# KHOI_NGUON.net
KiCad netlist of a schematic drawn in Altium Designer
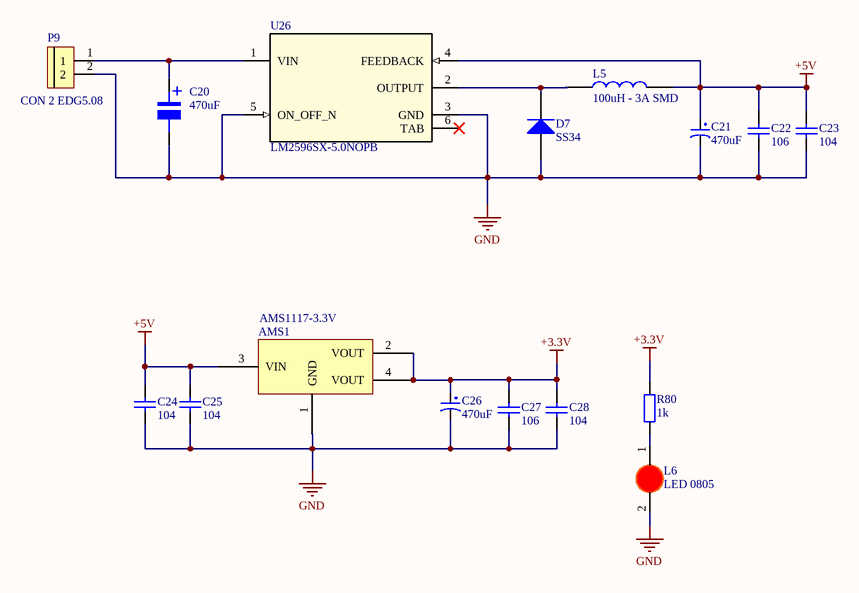
[diagram p0: KHOI_NGUON.SchDoc]

(export (version "E")
  (design (tool "Eeschema 10.0.6"))
  (components
    (comp (ref "AMS1")
      (value "AMS1117-3.3V")
      (footprint "SOT223")
      (description "Dán")
      (libsource (lib "Altium_Lib_by_KhueNguyenCreator") (part "AMS1117 SMD"))
    )
    (comp (ref "C20")
      (value "470uF")
      (footprint "tu nhom 8 (f)")
      (description "Dán")
      (libsource (lib "Altium_Lib_by_KhueNguyenCreator") (part "Tu Nhom 470uF 16V"))
    )
    (comp (ref "C21")
      (value "470uF")
      (footprint "tu hoa 8mm")
      (description "Cắm")
      (libsource (lib "Altium_Lib_by_KhueNguyenCreator") (part "Tu Hoa 470uF 16V 8x11"))
    )
    (comp (ref "C22")
      (value "106")
      (footprint "tu 0805")
      (description "Dán")
      (libsource (lib "Altium_Lib_by_KhueNguyenCreator") (part "Tu 0805 106 16V 10%"))
    )
    (comp (ref "C23")
      (value "104")
      (footprint "tu 0805")
      (description "Dán")
      (libsource (lib "Altium_Lib_by_KhueNguyenCreator") (part "Tu 0805 104 50V 10%"))
    )
    (comp (ref "C24")
      (value "104")
      (footprint "tu 0805")
      (description "Dán")
      (libsource (lib "Altium_Lib_by_KhueNguyenCreator") (part "Tu 0805 104 50V 10%"))
    )
    (comp (ref "C25")
      (value "104")
      (footprint "tu 0805")
      (description "Dán")
      (libsource (lib "Altium_Lib_by_KhueNguyenCreator") (part "Tu 0805 104 50V 10%"))
    )
    (comp (ref "C26")
      (value "470uF")
      (footprint "tu hoa 8mm")
      (description "Cắm")
      (libsource (lib "Altium_Lib_by_KhueNguyenCreator") (part "Tu Hoa 470uF 16V 8x11"))
    )
    (comp (ref "C27")
      (value "106")
      (footprint "tu 0805")
      (description "Dán")
      (libsource (lib "Altium_Lib_by_KhueNguyenCreator") (part "Tu 0805 106 16V 10%"))
    )
    (comp (ref "C28")
      (value "104")
      (footprint "tu 0805")
      (description "Dán")
      (libsource (lib "Altium_Lib_by_KhueNguyenCreator") (part "Tu 0805 104 50V 10%"))
    )
    (comp (ref "D7")
      (value "SS34")
      (footprint "DIODE SMA")
      (description "Dán")
      (libsource (lib "Altium_Lib_by_KhueNguyenCreator") (part "Diode SS34 ( 1N5822 )"))
    )
    (comp (ref "L5")
      (value "100uH - 3A SMD")
      (footprint "Cuon Cam 12x12x10")
      (description "Dán")
      (libsource (lib "Altium_Lib_by_KhueNguyenCreator") (part "CUON CAM 100uH SMD"))
    )
    (comp (ref "L6")
      (value "LED 0805")
      (footprint "LED-0805-Red")
      (description "Dán")
      (libsource (lib "Altium_Lib_by_KhueNguyenCreator") (part "LED 0805 Do"))
    )
    (comp (ref "P9")
      (value "CON 2 EDG5.08")
      (footprint "CON 2 2EDG5.08")
      (description "Cắm")
      (libsource (lib "Altium_Lib_by_KhueNguyenCreator") (part "CON 2 EDG5.08"))
    )
    (comp (ref "R80")
      (value "1k")
      (footprint "tro smd 0805")
      (description "Dán")
      (libsource (lib "Altium_Lib_by_KhueNguyenCreator") (part "Tro 0805 1% 1k"))
    )
    (comp (ref "U26")
      (value "LM2596SX-5.0NOPB")
      (footprint "KTT0005B")
      (description "No Description Available")
      (fields
        (field (name "PARTNUMBER") "LM2596SX-ADJ/NOPB")
        (field (name "ALTERNATE_PARTNUMBER") "LM2596S-ADJ/NOPB")
      )
      (libsource (lib "LM2596SX-5P0NOPB") (part "LM2596SX-5.0NOPB"))
    )
  )
  (nets
    (net (code "1") (name "+3.3V") (class "Default")
      (node (ref "AMS1") (pin "2") (pinfunction "VOUT_2") (pintype "passive"))
      (node (ref "AMS1") (pin "4") (pinfunction "VOUT_4") (pintype "passive"))
      (node (ref "C26") (pin "1") (pinfunction "1_1") (pintype "passive"))
      (node (ref "C27") (pin "1") (pinfunction "1_1") (pintype "passive"))
      (node (ref "C28") (pin "1") (pinfunction "1_1") (pintype "passive"))
      (node (ref "R80") (pin "1") (pinfunction "1_1") (pintype "passive"))
    )
    (net (code "2") (name "+5V") (class "Default")
      (node (ref "AMS1") (pin "3") (pinfunction "VIN_3") (pintype "passive"))
      (node (ref "C21") (pin "1") (pinfunction "1_1") (pintype "passive"))
      (node (ref "C22") (pin "1") (pinfunction "1_1") (pintype "passive"))
      (node (ref "C23") (pin "1") (pinfunction "1_1") (pintype "passive"))
      (node (ref "C24") (pin "1") (pinfunction "1_1") (pintype "passive"))
      (node (ref "C25") (pin "1") (pinfunction "1_1") (pintype "passive"))
      (node (ref "L5") (pin "2") (pinfunction "2_2") (pintype "passive"))
      (node (ref "U26") (pin "4") (pinfunction "FEEDBACK_4") (pintype "input"))
    )
    (net (code "3") (name "GND") (class "Default")
      (node (ref "AMS1") (pin "1") (pinfunction "GND_1") (pintype "passive"))
      (node (ref "C20") (pin "2") (pinfunction "2_2") (pintype "passive"))
      (node (ref "C21") (pin "2") (pinfunction "2_2") (pintype "passive"))
      (node (ref "C22") (pin "2") (pinfunction "2_2") (pintype "passive"))
      (node (ref "C23") (pin "2") (pinfunction "2_2") (pintype "passive"))
      (node (ref "C24") (pin "2") (pinfunction "2_2") (pintype "passive"))
      (node (ref "C25") (pin "2") (pinfunction "2_2") (pintype "passive"))
      (node (ref "C26") (pin "2") (pinfunction "2_2") (pintype "passive"))
      (node (ref "C27") (pin "2") (pinfunction "2_2") (pintype "passive"))
      (node (ref "C28") (pin "2") (pinfunction "2_2") (pintype "passive"))
      (node (ref "D7") (pin "1") (pinfunction "A_1") (pintype "passive"))
      (node (ref "L6") (pin "2") (pinfunction "K_2") (pintype "passive"))
      (node (ref "P9") (pin "2") (pinfunction "2_2") (pintype "passive"))
      (node (ref "U26") (pin "3") (pinfunction "GND_3") (pintype "power_in"))
      (node (ref "U26") (pin "5") (pinfunction "ON_OFF_N_5") (pintype "input"))
    )
    (net (code "4") (name "Net-(D7-K)") (class "Default")
      (node (ref "D7") (pin "2") (pinfunction "K_2") (pintype "passive"))
      (node (ref "L5") (pin "1") (pinfunction "1_1") (pintype "passive"))
      (node (ref "U26") (pin "2") (pinfunction "OUTPUT_2") (pintype "power_in"))
    )
    (net (code "5") (name "Net-(L6-A)") (class "Default")
      (node (ref "L6") (pin "1") (pinfunction "A_1") (pintype "passive"))
      (node (ref "R80") (pin "2") (pinfunction "2_2") (pintype "passive"))
    )
    (net (code "6") (name "Net-(U26-VIN)") (class "Default")
      (node (ref "C20") (pin "1") (pinfunction "1_1") (pintype "passive"))
      (node (ref "P9") (pin "1") (pinfunction "1_1") (pintype "passive"))
      (node (ref "U26") (pin "1") (pinfunction "VIN_1") (pintype "power_in"))
    )
    (net (code "7") (name "unconnected-(U26-TAB-Pad6)") (class "Default")
      (node (ref "U26") (pin "6") (pinfunction "TAB_6") (pintype "power_in+no_connect"))
    )
  )
)
